# Rear_Servo_Supply.net
KiCad netlist of a schematic drawn in Altium Designer
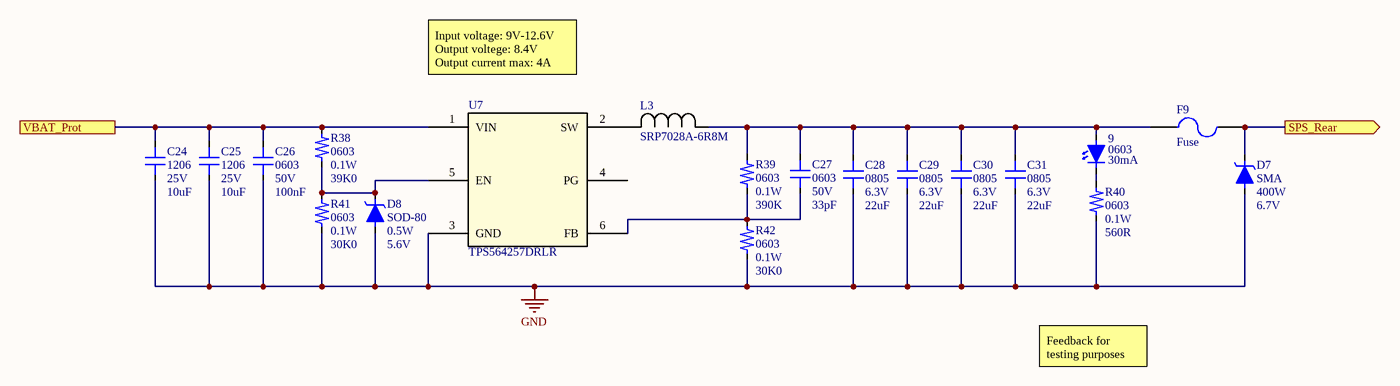
[diagram p0: Rear_Servo_Supply.SchDoc]

(export (version "E")
  (design (tool "Eeschema 10.0.6"))
  (components
    (comp (ref "9")
      (value "0603")
      (footprint "LED_0603")
      (fields
        (field (name "PART NUMBER") "FYLS-0603UGC")
        (field (name "TOLERANCE") "5%")
        (field (name "RATING") "30mA")
      )
      (libsource (lib "Components") (part "Diode_LED"))
    )
    (comp (ref "C24")
      (value "1206")
      (footprint "C_1206")
      (fields
        (field (name "TOLERANCE") "10%")
        (field (name "PART NUMBER") "C3216X7R1E106K160AB")
        (field (name "RATING") "25V")
        (field (name "ALTIUM_VALUE") "10uF")
      )
      (libsource (lib "Components") (part "Capacitor_Chip"))
    )
    (comp (ref "C25")
      (value "1206")
      (footprint "C_1206")
      (fields
        (field (name "TOLERANCE") "10%")
        (field (name "PART NUMBER") "C3216X7R1E106K160AB")
        (field (name "RATING") "25V")
        (field (name "ALTIUM_VALUE") "10uF")
      )
      (libsource (lib "Components") (part "Capacitor_Chip"))
    )
    (comp (ref "C26")
      (value "0603")
      (footprint "C_0603")
      (fields
        (field (name "TOLERANCE") "10%")
        (field (name "PART NUMBER") "CC0603KRX7R9BB104")
        (field (name "RATING") "50V")
        (field (name "ALTIUM_VALUE") "100nF")
        (field (name "NI PART NUMBER") "716340-01")
      )
      (libsource (lib "Components") (part "Capacitor_Chip"))
    )
    (comp (ref "C27")
      (value "0603")
      (footprint "C_0603")
      (fields
        (field (name "TOLERANCE") "5%")
        (field (name "PART NUMBER") "CL10C330JB8NNNC")
        (field (name "RATING") "50V")
        (field (name "ALTIUM_VALUE") "33pF")
        (field (name "NI PART NUMBER") "715511-01")
      )
      (libsource (lib "Components") (part "Capacitor_Chip"))
    )
    (comp (ref "C28")
      (value "0805")
      (footprint "C_0805")
      (fields
        (field (name "TOLERANCE") "20%")
        (field (name "PART NUMBER") "CL21A226MQQNNNG")
        (field (name "RATING") "6.3V")
        (field (name "ALTIUM_VALUE") "22uF")
      )
      (libsource (lib "Components") (part "Capacitor_Chip"))
    )
    (comp (ref "C29")
      (value "0805")
      (footprint "C_0805")
      (fields
        (field (name "TOLERANCE") "20%")
        (field (name "PART NUMBER") "CL21A226MQQNNNG")
        (field (name "RATING") "6.3V")
        (field (name "ALTIUM_VALUE") "22uF")
      )
      (libsource (lib "Components") (part "Capacitor_Chip"))
    )
    (comp (ref "C30")
      (value "0805")
      (footprint "C_0805")
      (fields
        (field (name "TOLERANCE") "20%")
        (field (name "PART NUMBER") "CL21A226MQQNNNG")
        (field (name "RATING") "6.3V")
        (field (name "ALTIUM_VALUE") "22uF")
      )
      (libsource (lib "Components") (part "Capacitor_Chip"))
    )
    (comp (ref "C31")
      (value "0805")
      (footprint "C_0805")
      (fields
        (field (name "TOLERANCE") "20%")
        (field (name "PART NUMBER") "CL21A226MQQNNNG")
        (field (name "RATING") "6.3V")
        (field (name "ALTIUM_VALUE") "22uF")
      )
      (libsource (lib "Components") (part "Capacitor_Chip"))
    )
    (comp (ref "D7")
      (value "SMA")
      (footprint "SMA")
      (fields
        (field (name "PART NUMBER") "SMAJ5.0A")
        (field (name "TOLERANCE") "5%")
        (field (name "RATING") "400W")
        (field (name "ALTIUM_VALUE") "6.7V")
      )
      (libsource (lib "Components") (part "Diode_Transient_Sup"))
    )
    (comp (ref "D8")
      (value "SOD-80")
      (footprint "SOD-80")
      (fields
        (field (name "PART NUMBER") "BZV55C5V6")
        (field (name "RATING") "0.5W")
        (field (name "ALTIUM_VALUE") "5.6V")
      )
      (libsource (lib "Components") (part "Diode_Zener"))
    )
    (comp (ref "F9")
      (value "Fuse")
      (footprint "F_2410")
      (fields (field (name "PART NUMBER") "0451003.MRL"))
      (libsource (lib "Components") (part "Fuse"))
    )
    (comp (ref "L3")
      (value "SRP7028A-6R8M")
      (footprint "IND_SRP7028A-6R8M_BRN")
      (description "No Description Available")
      (fields (field (name "COPYRIGHT") "Copyright (C) 2023 Ultra Librarian. All rights reserved."))
      (libsource (lib "SRP7028A-6R8M") (part "SRP7028A-6R8M"))
    )
    (comp (ref "R38")
      (value "0603")
      (footprint "R_0603")
      (fields
        (field (name "TOLERANCE") "5%")
        (field (name "PART NUMBER") "CR-03JL7---39K")
        (field (name "RATING") "0.1W")
        (field (name "ALTIUM_VALUE") "39K0")
        (field (name "NI PART NUMBER") "613245-01")
      )
      (libsource (lib "Components") (part "Resistor_Chip"))
    )
    (comp (ref "R39")
      (value "0603")
      (footprint "R_0603")
      (fields
        (field (name "TOLERANCE") "1%")
        (field (name "PART NUMBER") "CR-03FL7--390K")
        (field (name "RATING") "0.1W")
        (field (name "ALTIUM_VALUE") "390K")
      )
      (libsource (lib "Components") (part "Resistor_Chip"))
    )
    (comp (ref "R40")
      (value "0603")
      (footprint "R_0603")
      (fields
        (field (name "TOLERANCE") "1%")
        (field (name "PART NUMBER") "CR-03FL7--560R")
        (field (name "RATING") "0.1W")
        (field (name "ALTIUM_VALUE") "560R")
        (field (name "NI PART NUMBER") "612556-01")
      )
      (libsource (lib "Components") (part "Resistor_Chip"))
    )
    (comp (ref "R41")
      (value "0603")
      (footprint "R_0603")
      (fields
        (field (name "TOLERANCE") "1%")
        (field (name "PART NUMBER") "CR-03FL7---30K")
        (field (name "RATING") "0.1W")
        (field (name "ALTIUM_VALUE") "30K0")
        (field (name "NI PART NUMBER") "612699-01")
      )
      (libsource (lib "Components") (part "Resistor_Chip"))
    )
    (comp (ref "R42")
      (value "0603")
      (footprint "R_0603")
      (fields
        (field (name "TOLERANCE") "1%")
        (field (name "PART NUMBER") "CR-03FL7---30K")
        (field (name "RATING") "0.1W")
        (field (name "ALTIUM_VALUE") "30K0")
        (field (name "NI PART NUMBER") "612699-01")
      )
      (libsource (lib "Components") (part "Resistor_Chip"))
    )
    (comp (ref "U7")
      (value "TPS564257DRLR")
      (footprint "TPS564242DRLR_TEX")
      (description "No Description Available")
      (fields (field (name "COPYRIGHT") "Copyright (C) 2023 Ultra Librarian. All rights reserved."))
      (libsource (lib "TPS564257DRLR") (part "TPS564257DRLR"))
    )
  )
  (nets
    (net (code "1") (name "/SPS_Rear") (class "Default")
      (node (ref "D7") (pin "1") (pinfunction "DC_1") (pintype "passive"))
      (node (ref "F9") (pin "2") (pinfunction "2_2") (pintype "passive"))
    )
    (net (code "2") (name "/VBAT_Prot") (class "Default")
      (node (ref "C24") (pin "2") (pinfunction "C2_2") (pintype "passive"))
      (node (ref "C25") (pin "2") (pinfunction "C2_2") (pintype "passive"))
      (node (ref "C26") (pin "2") (pinfunction "C2_2") (pintype "passive"))
      (node (ref "R38") (pin "2") (pinfunction "R2_2") (pintype "passive"))
      (node (ref "U7") (pin "1") (pinfunction "VIN_1") (pintype "power_in"))
    )
    (net (code "3") (name "GND") (class "Default")
      (node (ref "C24") (pin "1") (pinfunction "C1_1") (pintype "passive"))
      (node (ref "C25") (pin "1") (pinfunction "C1_1") (pintype "passive"))
      (node (ref "C26") (pin "1") (pinfunction "C1_1") (pintype "passive"))
      (node (ref "C28") (pin "1") (pinfunction "C1_1") (pintype "passive"))
      (node (ref "C29") (pin "1") (pinfunction "C1_1") (pintype "passive"))
      (node (ref "C30") (pin "1") (pinfunction "C1_1") (pintype "passive"))
      (node (ref "C31") (pin "1") (pinfunction "C1_1") (pintype "passive"))
      (node (ref "D7") (pin "2") (pinfunction "DA_2") (pintype "passive"))
      (node (ref "D8") (pin "2") (pinfunction "DA_2") (pintype "passive"))
      (node (ref "R40") (pin "1") (pinfunction "R1_1") (pintype "passive"))
      (node (ref "R41") (pin "1") (pinfunction "R1_1") (pintype "passive"))
      (node (ref "R42") (pin "1") (pinfunction "R1_1") (pintype "passive"))
      (node (ref "U7") (pin "3") (pinfunction "GND_3") (pintype "power_in"))
    )
    (net (code "4") (name "Net-(9-DA)") (class "Default")
      (node (ref "9") (pin "2") (pinfunction "DA_2") (pintype "passive"))
      (node (ref "C27") (pin "2") (pinfunction "C2_2") (pintype "passive"))
      (node (ref "C28") (pin "2") (pinfunction "C2_2") (pintype "passive"))
      (node (ref "C29") (pin "2") (pinfunction "C2_2") (pintype "passive"))
      (node (ref "C30") (pin "2") (pinfunction "C2_2") (pintype "passive"))
      (node (ref "C31") (pin "2") (pinfunction "C2_2") (pintype "passive"))
      (node (ref "F9") (pin "1") (pinfunction "1_1") (pintype "passive"))
      (node (ref "L3") (pin "1") (pinfunction "1_1") (pintype "passive"))
      (node (ref "R39") (pin "2") (pinfunction "R2_2") (pintype "passive"))
    )
    (net (code "5") (name "Net-(9-DC)") (class "Default")
      (node (ref "9") (pin "1") (pinfunction "DC_1") (pintype "passive"))
      (node (ref "R40") (pin "2") (pinfunction "R2_2") (pintype "passive"))
    )
    (net (code "6") (name "Net-(C27-C1)") (class "Default")
      (node (ref "C27") (pin "1") (pinfunction "C1_1") (pintype "passive"))
      (node (ref "R39") (pin "1") (pinfunction "R1_1") (pintype "passive"))
      (node (ref "R42") (pin "2") (pinfunction "R2_2") (pintype "passive"))
      (node (ref "U7") (pin "6") (pinfunction "FB_6") (pintype "passive"))
    )
    (net (code "7") (name "Net-(D8-DC)") (class "Default")
      (node (ref "D8") (pin "1") (pinfunction "DC_1") (pintype "passive"))
      (node (ref "R38") (pin "1") (pinfunction "R1_1") (pintype "passive"))
      (node (ref "R41") (pin "2") (pinfunction "R2_2") (pintype "passive"))
      (node (ref "U7") (pin "5") (pinfunction "EN_5") (pintype "passive"))
    )
    (net (code "8") (name "Net-(U7-SW)") (class "Default")
      (node (ref "L3") (pin "2") (pinfunction "2_2") (pintype "passive"))
      (node (ref "U7") (pin "2") (pinfunction "SW_2") (pintype "power_in"))
    )
    (net (code "9") (name "unconnected-(U7-PG-Pad4)") (class "Default")
      (node (ref "U7") (pin "4") (pinfunction "PG_4") (pintype "passive"))
    )
  )
)
